# MB1063.net
KiCad netlist of a schematic drawn in Altium Designer
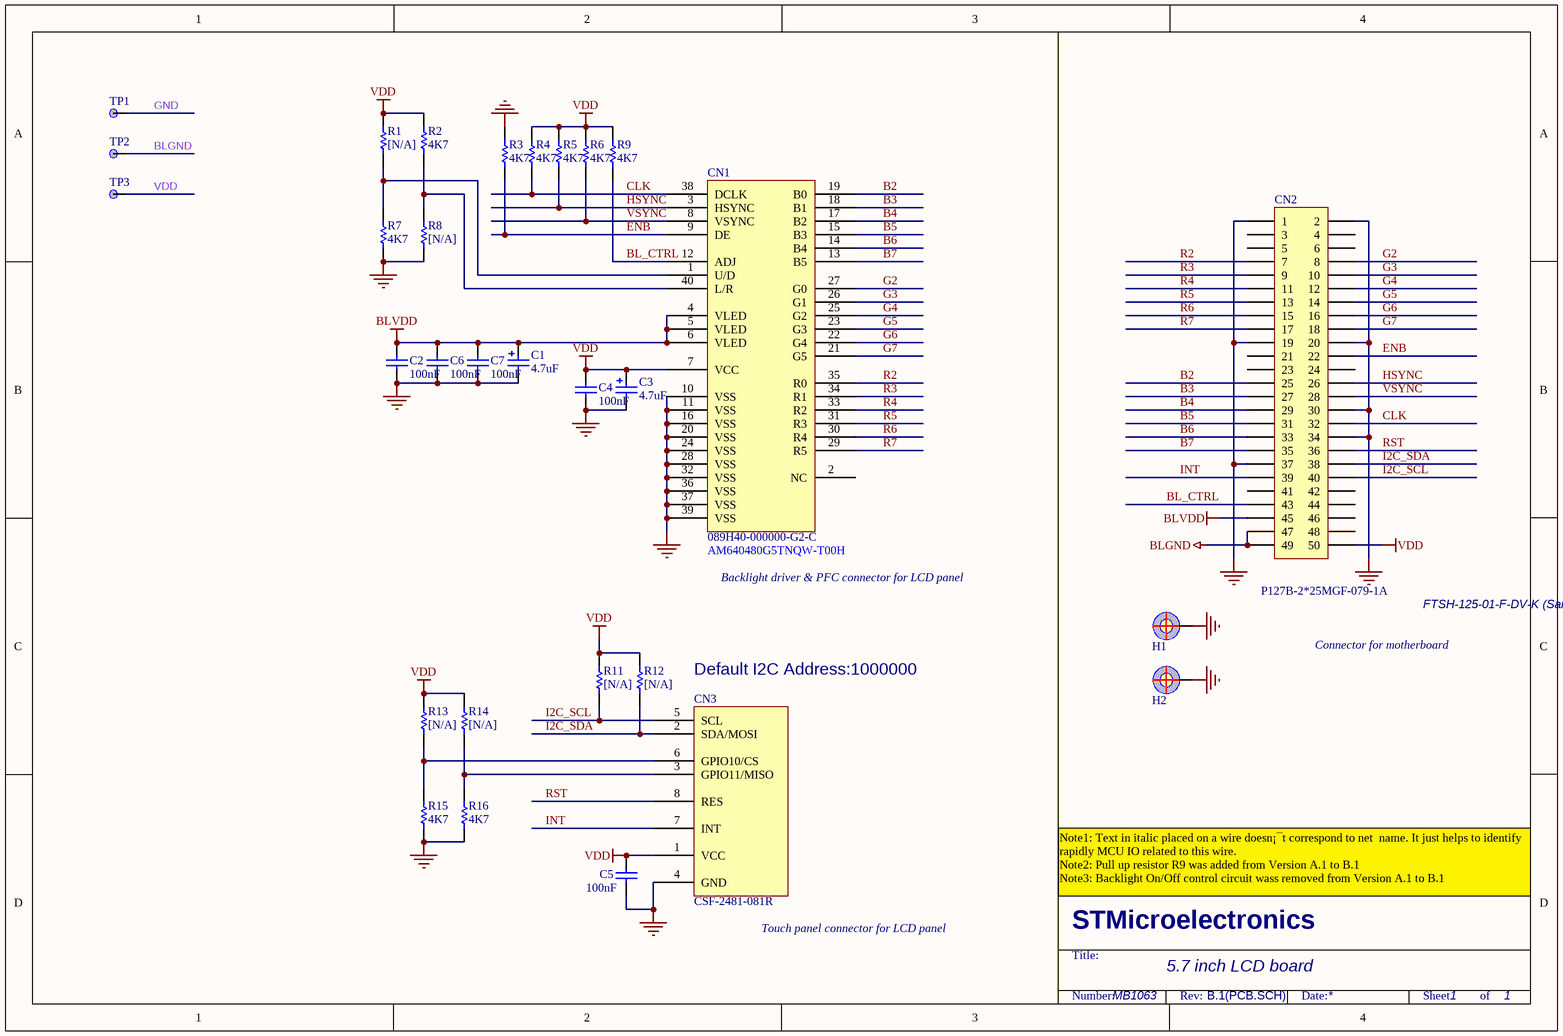
[diagram p0: MB1063.SchDoc]

(export (version "E")
  (design (tool "Eeschema 10.0.6"))
  (components
    (comp (ref "C1")
      (value "4.7uF")
      (footprint "TAN-A")
      (description "Polarized Capacitor (Radial)")
      (fields (field (name "PUBLISHER") "Altium Limited"))
      (libsource (lib "Miscellaneous Devices") (part "Cap Pol1"))
    )
    (comp (ref "C2")
      (value "100nF")
      (footprint "0603C")
      (description "Capacitor")
      (fields (field (name "PUBLISHER") "Altium Limited"))
      (libsource (lib "Miscellaneous Devices") (part "CAP"))
    )
    (comp (ref "C3")
      (value "4.7uF")
      (footprint "TAN-A")
      (description "Polarized Capacitor (Radial)")
      (fields (field (name "PUBLISHER") "Altium Limited"))
      (libsource (lib "Miscellaneous Devices") (part "Cap Pol1"))
    )
    (comp (ref "C4")
      (value "100nF")
      (footprint "0603C")
      (description "Capacitor")
      (fields (field (name "PUBLISHER") "Altium Limited"))
      (libsource (lib "Miscellaneous Devices") (part "CAP"))
    )
    (comp (ref "C5")
      (value "100nF")
      (footprint "0603C")
      (description "Capacitor")
      (fields (field (name "PUBLISHER") "Altium Limited"))
      (libsource (lib "Miscellaneous Devices") (part "CAP"))
    )
    (comp (ref "C6")
      (value "100nF")
      (footprint "0603C")
      (description "Capacitor")
      (fields (field (name "PUBLISHER") "Altium Limited"))
      (libsource (lib "Miscellaneous Devices") (part "CAP"))
    )
    (comp (ref "C7")
      (value "100nF")
      (footprint "0603C")
      (description "Capacitor")
      (fields (field (name "PUBLISHER") "Altium Limited"))
      (libsource (lib "Miscellaneous Devices") (part "CAP"))
    )
    (comp (ref "CN1")
      (value "089H40-000000-G2-C")
      (footprint "FPC40_0R5_089H40LY-FPC_REV")
      (libsource (lib "MB1063") (part "089H40-000000-G2-C"))
    )
    (comp (ref "CN2")
      (value "P127B-2*25MGF-079-1A")
      (footprint "FTSH-125-01-F-DV")
      (description "Header, 26-Pin, Dual row")
      (fields (field (name "PUBLISHER") "Altium Limited"))
      (libsource (lib "mb1045") (part "Header 25X2"))
    )
    (comp (ref "CN3")
      (value "CSF-2481-081R")
      (footprint "FPC8_0R5_089H08_LY-FPC_REV")
      (libsource (lib "MB1063") (part "CSF-2481-081R"))
    )
    (comp (ref "H1")
      (value "POSITION HOLE")
      (footprint "HOLE_C9D4R5")
      (libsource (lib "mb1045") (part "POSITION HOLE"))
    )
    (comp (ref "H2")
      (value "POSITION HOLE")
      (footprint "HOLE_C9D4R5")
      (libsource (lib "mb1045") (part "POSITION HOLE"))
    )
    (comp (ref "R1")
      (value "[N/A]")
      (footprint "0603R")
      (description "Resistor")
      (fields (field (name "PUBLISHER") "Altium Limited"))
      (libsource (lib "*") (part "Res1"))
    )
    (comp (ref "R2")
      (value "4K7")
      (footprint "0603R")
      (description "Resistor")
      (fields (field (name "PUBLISHER") "Altium Limited"))
      (libsource (lib "*") (part "Res1"))
    )
    (comp (ref "R3")
      (value "4K7")
      (footprint "0603R")
      (description "Resistor")
      (fields (field (name "PUBLISHER") "Altium Limited"))
      (libsource (lib "*") (part "Res1"))
    )
    (comp (ref "R4")
      (value "4K7")
      (footprint "0603R")
      (description "Resistor")
      (fields (field (name "PUBLISHER") "Altium Limited"))
      (libsource (lib "*") (part "Res1"))
    )
    (comp (ref "R5")
      (value "4K7")
      (footprint "0603R")
      (description "Resistor")
      (fields (field (name "PUBLISHER") "Altium Limited"))
      (libsource (lib "*") (part "Res1"))
    )
    (comp (ref "R6")
      (value "4K7")
      (footprint "0603R")
      (description "Resistor")
      (fields (field (name "PUBLISHER") "Altium Limited"))
      (libsource (lib "*") (part "Res1"))
    )
    (comp (ref "R7")
      (value "4K7")
      (footprint "0603R")
      (description "Resistor")
      (fields (field (name "PUBLISHER") "Altium Limited"))
      (libsource (lib "*") (part "Res1"))
    )
    (comp (ref "R8")
      (value "[N/A]")
      (footprint "0603R")
      (description "Resistor")
      (fields (field (name "PUBLISHER") "Altium Limited"))
      (libsource (lib "*") (part "Res1"))
    )
    (comp (ref "R9")
      (value "4K7")
      (footprint "0603R")
      (description "Resistor")
      (fields (field (name "PUBLISHER") "Altium Limited"))
      (libsource (lib "*") (part "Res1"))
    )
    (comp (ref "R11")
      (value "[N/A]")
      (footprint "0603R")
      (description "Resistor")
      (fields (field (name "PUBLISHER") "Altium Limited"))
      (libsource (lib "*") (part "Res1"))
    )
    (comp (ref "R12")
      (value "[N/A]")
      (footprint "0603R")
      (description "Resistor")
      (fields (field (name "PUBLISHER") "Altium Limited"))
      (libsource (lib "*") (part "Res1"))
    )
    (comp (ref "R13")
      (value "[N/A]")
      (footprint "0603R")
      (description "Resistor")
      (fields (field (name "PUBLISHER") "Altium Limited"))
      (libsource (lib "*") (part "Res1"))
    )
    (comp (ref "R14")
      (value "[N/A]")
      (footprint "0603R")
      (description "Resistor")
      (fields (field (name "PUBLISHER") "Altium Limited"))
      (libsource (lib "*") (part "Res1"))
    )
    (comp (ref "R15")
      (value "4K7")
      (footprint "0603R")
      (description "Resistor")
      (fields (field (name "PUBLISHER") "Altium Limited"))
      (libsource (lib "*") (part "Res1"))
    )
    (comp (ref "R16")
      (value "4K7")
      (footprint "0603R")
      (description "Resistor")
      (fields (field (name "PUBLISHER") "Altium Limited"))
      (libsource (lib "*") (part "Res1"))
    )
    (comp (ref "TP1") (value "~") (footprint "TP") (libsource (lib "*") (part "TP")))
    (comp (ref "TP2") (value "~") (footprint "TP") (libsource (lib "*") (part "TP")))
    (comp (ref "TP3") (value "~") (footprint "TP") (libsource (lib "*") (part "TP")))
  )
  (nets
    (net (code "1") (name "/B2") (class "Default")
      (node (ref "CN1") (pin "19") (pinfunction "B0_19") (pintype "passive"))
      (node (ref "CN2") (pin "25") (pinfunction "25_25") (pintype "passive"))
    )
    (net (code "2") (name "/B3") (class "Default")
      (node (ref "CN1") (pin "18") (pinfunction "B1_18") (pintype "passive"))
      (node (ref "CN2") (pin "27") (pinfunction "27_27") (pintype "passive"))
    )
    (net (code "3") (name "/B4") (class "Default")
      (node (ref "CN1") (pin "17") (pinfunction "B2_17") (pintype "passive"))
      (node (ref "CN2") (pin "29") (pinfunction "29_29") (pintype "passive"))
    )
    (net (code "4") (name "/B5") (class "Default")
      (node (ref "CN1") (pin "15") (pinfunction "B3_15") (pintype "passive"))
      (node (ref "CN2") (pin "31") (pinfunction "31_31") (pintype "passive"))
    )
    (net (code "5") (name "/B6") (class "Default")
      (node (ref "CN1") (pin "14") (pinfunction "B4_14") (pintype "passive"))
      (node (ref "CN2") (pin "33") (pinfunction "33_33") (pintype "passive"))
    )
    (net (code "6") (name "/B7") (class "Default")
      (node (ref "CN1") (pin "13") (pinfunction "B5_13") (pintype "passive"))
      (node (ref "CN2") (pin "35") (pinfunction "35_35") (pintype "passive"))
    )
    (net (code "7") (name "/BL_CTRL") (class "Default")
      (node (ref "CN1") (pin "12") (pinfunction "ADJ_12") (pintype "passive"))
      (node (ref "CN2") (pin "43") (pinfunction "43_43") (pintype "passive"))
      (node (ref "R9") (pin "2") (pinfunction "2_2") (pintype "passive"))
    )
    (net (code "8") (name "/CLK") (class "Default")
      (node (ref "CN1") (pin "38") (pinfunction "DCLK_38") (pintype "passive"))
      (node (ref "CN2") (pin "32") (pinfunction "32_32") (pintype "passive"))
      (node (ref "R4") (pin "2") (pinfunction "2_2") (pintype "passive"))
    )
    (net (code "9") (name "/ENB") (class "Default")
      (node (ref "CN1") (pin "9") (pinfunction "DE_9") (pintype "passive"))
      (node (ref "CN2") (pin "22") (pinfunction "22_22") (pintype "passive"))
      (node (ref "R3") (pin "2") (pinfunction "2_2") (pintype "passive"))
    )
    (net (code "10") (name "/G2") (class "Default")
      (node (ref "CN1") (pin "27") (pinfunction "G0_27") (pintype "passive"))
      (node (ref "CN2") (pin "8") (pinfunction "8_8") (pintype "passive"))
    )
    (net (code "11") (name "/G3") (class "Default")
      (node (ref "CN1") (pin "26") (pinfunction "G1_26") (pintype "passive"))
      (node (ref "CN2") (pin "10") (pinfunction "10_10") (pintype "passive"))
    )
    (net (code "12") (name "/G4") (class "Default")
      (node (ref "CN1") (pin "25") (pinfunction "G2_25") (pintype "passive"))
      (node (ref "CN2") (pin "12") (pinfunction "12_12") (pintype "passive"))
    )
    (net (code "13") (name "/G5") (class "Default")
      (node (ref "CN1") (pin "23") (pinfunction "G3_23") (pintype "passive"))
      (node (ref "CN2") (pin "14") (pinfunction "14_14") (pintype "passive"))
    )
    (net (code "14") (name "/G6") (class "Default")
      (node (ref "CN1") (pin "22") (pinfunction "G4_22") (pintype "passive"))
      (node (ref "CN2") (pin "16") (pinfunction "16_16") (pintype "passive"))
    )
    (net (code "15") (name "/G7") (class "Default")
      (node (ref "CN1") (pin "21") (pinfunction "G5_21") (pintype "passive"))
      (node (ref "CN2") (pin "18") (pinfunction "18_18") (pintype "passive"))
    )
    (net (code "16") (name "/HSYNC") (class "Default")
      (node (ref "CN1") (pin "3") (pinfunction "HSYNC_3") (pintype "passive"))
      (node (ref "CN2") (pin "26") (pinfunction "26_26") (pintype "passive"))
      (node (ref "R5") (pin "2") (pinfunction "2_2") (pintype "passive"))
    )
    (net (code "17") (name "/I2C_SCL") (class "Default")
      (node (ref "CN2") (pin "40") (pinfunction "40_40") (pintype "passive"))
      (node (ref "CN3") (pin "5") (pinfunction "SCL_5") (pintype "passive"))
      (node (ref "R11") (pin "2") (pinfunction "2_2") (pintype "passive"))
    )
    (net (code "18") (name "/I2C_SDA") (class "Default")
      (node (ref "CN2") (pin "38") (pinfunction "38_38") (pintype "passive"))
      (node (ref "CN3") (pin "2") (pinfunction "SDA/MOSI_2") (pintype "passive"))
      (node (ref "R12") (pin "2") (pinfunction "2_2") (pintype "passive"))
    )
    (net (code "19") (name "/INT") (class "Default")
      (node (ref "CN2") (pin "39") (pinfunction "39_39") (pintype "passive"))
      (node (ref "CN3") (pin "7") (pinfunction "INT_7") (pintype "passive"))
    )
    (net (code "20") (name "/R2") (class "Default")
      (node (ref "CN1") (pin "35") (pinfunction "R0_35") (pintype "passive"))
      (node (ref "CN2") (pin "7") (pinfunction "7_7") (pintype "passive"))
    )
    (net (code "21") (name "/R3") (class "Default")
      (node (ref "CN1") (pin "34") (pinfunction "R1_34") (pintype "passive"))
      (node (ref "CN2") (pin "9") (pinfunction "9_9") (pintype "passive"))
    )
    (net (code "22") (name "/R4") (class "Default")
      (node (ref "CN1") (pin "33") (pinfunction "R2_33") (pintype "passive"))
      (node (ref "CN2") (pin "11") (pinfunction "11_11") (pintype "passive"))
    )
    (net (code "23") (name "/R5") (class "Default")
      (node (ref "CN1") (pin "31") (pinfunction "R3_31") (pintype "passive"))
      (node (ref "CN2") (pin "13") (pinfunction "13_13") (pintype "passive"))
    )
    (net (code "24") (name "/R6") (class "Default")
      (node (ref "CN1") (pin "30") (pinfunction "R4_30") (pintype "passive"))
      (node (ref "CN2") (pin "15") (pinfunction "15_15") (pintype "passive"))
    )
    (net (code "25") (name "/R7") (class "Default")
      (node (ref "CN1") (pin "29") (pinfunction "R5_29") (pintype "passive"))
      (node (ref "CN2") (pin "17") (pinfunction "17_17") (pintype "passive"))
    )
    (net (code "26") (name "/RST") (class "Default")
      (node (ref "CN2") (pin "36") (pinfunction "36_36") (pintype "passive"))
      (node (ref "CN3") (pin "8") (pinfunction "RES_8") (pintype "passive"))
    )
    (net (code "27") (name "/VSYNC") (class "Default")
      (node (ref "CN1") (pin "8") (pinfunction "VSYNC_8") (pintype "passive"))
      (node (ref "CN2") (pin "28") (pinfunction "28_28") (pintype "passive"))
      (node (ref "R6") (pin "2") (pinfunction "2_2") (pintype "passive"))
    )
    (net (code "28") (name "BLGND") (class "Default")
      (node (ref "CN2") (pin "47") (pinfunction "47_47") (pintype "passive"))
      (node (ref "CN2") (pin "49") (pinfunction "49_49") (pintype "passive"))
      (node (ref "TP2") (pin "1") (pinfunction "1_1") (pintype "passive"))
    )
    (net (code "29") (name "BLVDD") (class "Default")
      (node (ref "C1") (pin "1") (pinfunction "1_1") (pintype "passive"))
      (node (ref "C2") (pin "2") (pinfunction "2_2") (pintype "passive"))
      (node (ref "C6") (pin "2") (pinfunction "2_2") (pintype "passive"))
      (node (ref "C7") (pin "2") (pinfunction "2_2") (pintype "passive"))
      (node (ref "CN1") (pin "4") (pinfunction "VLED_4") (pintype "passive"))
      (node (ref "CN1") (pin "5") (pinfunction "VLED_5") (pintype "passive"))
      (node (ref "CN1") (pin "6") (pinfunction "VLED_6") (pintype "passive"))
      (node (ref "CN2") (pin "45") (pinfunction "45_45") (pintype "passive"))
    )
    (net (code "30") (name "GND") (class "Default")
      (node (ref "C1") (pin "2") (pinfunction "2_2") (pintype "passive"))
      (node (ref "C2") (pin "1") (pinfunction "1_1") (pintype "passive"))
      (node (ref "C3") (pin "2") (pinfunction "2_2") (pintype "passive"))
      (node (ref "C4") (pin "1") (pinfunction "1_1") (pintype "passive"))
      (node (ref "C5") (pin "1") (pinfunction "1_1") (pintype "passive"))
      (node (ref "C6") (pin "1") (pinfunction "1_1") (pintype "passive"))
      (node (ref "C7") (pin "1") (pinfunction "1_1") (pintype "passive"))
      (node (ref "CN1") (pin "10") (pinfunction "VSS_10") (pintype "passive"))
      (node (ref "CN1") (pin "11") (pinfunction "VSS_11") (pintype "passive"))
      (node (ref "CN1") (pin "16") (pinfunction "VSS_16") (pintype "passive"))
      (node (ref "CN1") (pin "20") (pinfunction "VSS_20") (pintype "passive"))
      (node (ref "CN1") (pin "24") (pinfunction "VSS_24") (pintype "passive"))
      (node (ref "CN1") (pin "28") (pinfunction "VSS_28") (pintype "passive"))
      (node (ref "CN1") (pin "32") (pinfunction "VSS_32") (pintype "passive"))
      (node (ref "CN1") (pin "36") (pinfunction "VSS_36") (pintype "passive"))
      (node (ref "CN1") (pin "37") (pinfunction "VSS_37") (pintype "passive"))
      (node (ref "CN1") (pin "39") (pinfunction "VSS_39") (pintype "passive"))
      (node (ref "CN2") (pin "1") (pinfunction "1_1") (pintype "passive"))
      (node (ref "CN2") (pin "19") (pinfunction "19_19") (pintype "passive"))
      (node (ref "CN2") (pin "2") (pinfunction "2_2") (pintype "passive"))
      (node (ref "CN2") (pin "20") (pinfunction "20_20") (pintype "passive"))
      (node (ref "CN2") (pin "30") (pinfunction "30_30") (pintype "passive"))
      (node (ref "CN2") (pin "34") (pinfunction "34_34") (pintype "passive"))
      (node (ref "CN2") (pin "37") (pinfunction "37_37") (pintype "passive"))
      (node (ref "CN3") (pin "4") (pinfunction "GND_4") (pintype "passive"))
      (node (ref "H1") (pin "1") (pinfunction "1_1") (pintype "passive"))
      (node (ref "H2") (pin "1") (pinfunction "1_1") (pintype "passive"))
      (node (ref "R15") (pin "2") (pinfunction "2_2") (pintype "passive"))
      (node (ref "R16") (pin "2") (pinfunction "2_2") (pintype "passive"))
      (node (ref "R3") (pin "1") (pinfunction "1_1") (pintype "passive"))
      (node (ref "R7") (pin "2") (pinfunction "2_2") (pintype "passive"))
      (node (ref "R8") (pin "2") (pinfunction "2_2") (pintype "passive"))
      (node (ref "TP1") (pin "1") (pinfunction "1_1") (pintype "passive"))
    )
    (net (code "31") (name "Net-(CN1-L{slash}R)") (class "Default")
      (node (ref "CN1") (pin "40") (pinfunction "L/R_40") (pintype "passive"))
      (node (ref "R2") (pin "2") (pinfunction "2_2") (pintype "passive"))
      (node (ref "R8") (pin "1") (pinfunction "1_1") (pintype "passive"))
    )
    (net (code "32") (name "Net-(CN1-U{slash}D)") (class "Default")
      (node (ref "CN1") (pin "1") (pinfunction "U/D_1") (pintype "passive"))
      (node (ref "R1") (pin "2") (pinfunction "2_2") (pintype "passive"))
      (node (ref "R7") (pin "1") (pinfunction "1_1") (pintype "passive"))
    )
    (net (code "33") (name "Net-(CN3-GPIO10{slash}CS)") (class "Default")
      (node (ref "CN3") (pin "6") (pinfunction "GPIO10/CS_6") (pintype "passive"))
      (node (ref "R13") (pin "2") (pinfunction "2_2") (pintype "passive"))
      (node (ref "R15") (pin "1") (pinfunction "1_1") (pintype "passive"))
    )
    (net (code "34") (name "Net-(CN3-GPIO11{slash}MISO)") (class "Default")
      (node (ref "CN3") (pin "3") (pinfunction "GPIO11/MISO_3") (pintype "passive"))
      (node (ref "R14") (pin "2") (pinfunction "2_2") (pintype "passive"))
      (node (ref "R16") (pin "1") (pinfunction "1_1") (pintype "passive"))
    )
    (net (code "35") (name "VDD") (class "Default")
      (node (ref "C3") (pin "1") (pinfunction "1_1") (pintype "passive"))
      (node (ref "C4") (pin "2") (pinfunction "2_2") (pintype "passive"))
      (node (ref "C5") (pin "2") (pinfunction "2_2") (pintype "passive"))
      (node (ref "CN1") (pin "7") (pinfunction "VCC_7") (pintype "passive"))
      (node (ref "CN2") (pin "50") (pinfunction "50_50") (pintype "passive"))
      (node (ref "CN3") (pin "1") (pinfunction "VCC_1") (pintype "passive"))
      (node (ref "R1") (pin "1") (pinfunction "1_1") (pintype "passive"))
      (node (ref "R11") (pin "1") (pinfunction "1_1") (pintype "passive"))
      (node (ref "R12") (pin "1") (pinfunction "1_1") (pintype "passive"))
      (node (ref "R13") (pin "1") (pinfunction "1_1") (pintype "passive"))
      (node (ref "R14") (pin "1") (pinfunction "1_1") (pintype "passive"))
      (node (ref "R2") (pin "1") (pinfunction "1_1") (pintype "passive"))
      (node (ref "R4") (pin "1") (pinfunction "1_1") (pintype "passive"))
      (node (ref "R5") (pin "1") (pinfunction "1_1") (pintype "passive"))
      (node (ref "R6") (pin "1") (pinfunction "1_1") (pintype "passive"))
      (node (ref "R9") (pin "1") (pinfunction "1_1") (pintype "passive"))
      (node (ref "TP3") (pin "1") (pinfunction "1_1") (pintype "passive"))
    )
    (net (code "36") (name "unconnected-(CN1-NC-Pad2)") (class "Default")
      (node (ref "CN1") (pin "2") (pinfunction "NC_2") (pintype "passive"))
    )
    (net (code "37") (name "unconnected-(CN2-Pad3)") (class "Default")
      (node (ref "CN2") (pin "3") (pinfunction "3_3") (pintype "passive"))
    )
    (net (code "38") (name "unconnected-(CN2-Pad4)") (class "Default")
      (node (ref "CN2") (pin "4") (pinfunction "4_4") (pintype "passive"))
    )
    (net (code "39") (name "unconnected-(CN2-Pad5)") (class "Default")
      (node (ref "CN2") (pin "5") (pinfunction "5_5") (pintype "passive"))
    )
    (net (code "40") (name "unconnected-(CN2-Pad6)") (class "Default")
      (node (ref "CN2") (pin "6") (pinfunction "6_6") (pintype "passive"))
    )
    (net (code "41") (name "unconnected-(CN2-Pad21)") (class "Default")
      (node (ref "CN2") (pin "21") (pinfunction "21_21") (pintype "passive"))
    )
    (net (code "42") (name "unconnected-(CN2-Pad23)") (class "Default")
      (node (ref "CN2") (pin "23") (pinfunction "23_23") (pintype "passive"))
    )
    (net (code "43") (name "unconnected-(CN2-Pad24)") (class "Default")
      (node (ref "CN2") (pin "24") (pinfunction "24_24") (pintype "passive"))
    )
    (net (code "44") (name "unconnected-(CN2-Pad41)") (class "Default")
      (node (ref "CN2") (pin "41") (pinfunction "41_41") (pintype "passive"))
    )
    (net (code "45") (name "unconnected-(CN2-Pad42)") (class "Default")
      (node (ref "CN2") (pin "42") (pinfunction "42_42") (pintype "passive"))
    )
    (net (code "46") (name "unconnected-(CN2-Pad44)") (class "Default")
      (node (ref "CN2") (pin "44") (pinfunction "44_44") (pintype "passive"))
    )
    (net (code "47") (name "unconnected-(CN2-Pad46)") (class "Default")
      (node (ref "CN2") (pin "46") (pinfunction "46_46") (pintype "passive"))
    )
    (net (code "48") (name "unconnected-(CN2-Pad48)") (class "Default")
      (node (ref "CN2") (pin "48") (pinfunction "48_48") (pintype "passive"))
    )
  )
)
